# untitled.net
KiCad netlist of a schematic drawn in EAGLE
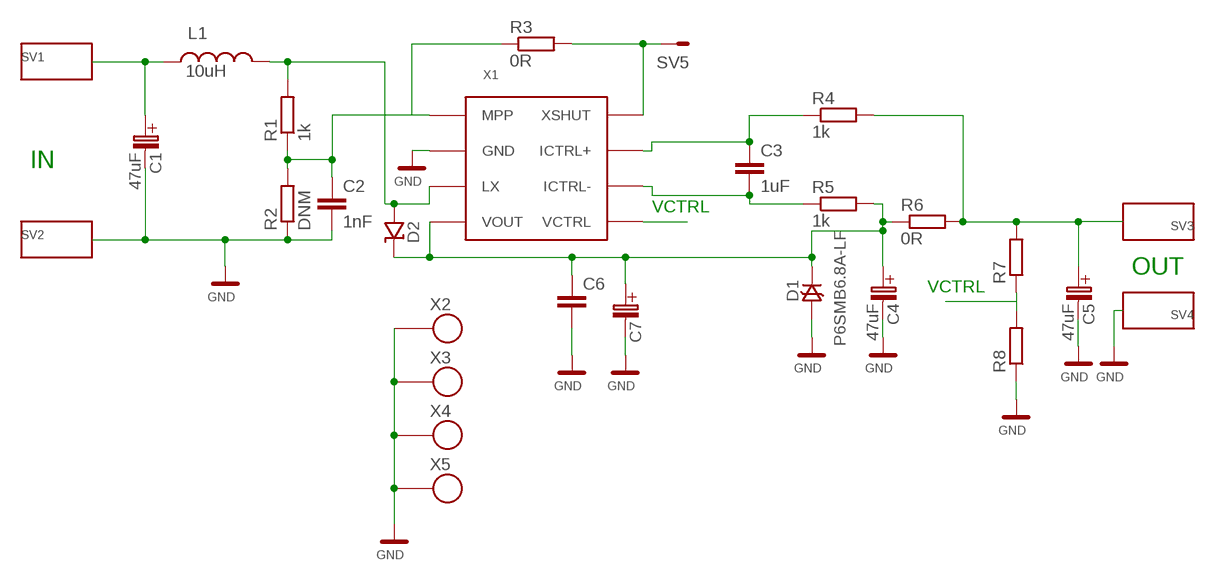
[diagram p0: schematic, sheet 1]

(export (version "E")
  (design (tool "Eeschema 10.0.6"))
  (components
    (comp (ref "C1") (value "47uF") (footprint "eagle-import:C") (libsource (lib "eagle-import") (part "C")))
    (comp (ref "C2")
      (value "1nF")
      (footprint "eagle-import:C0805")
      (libsource (lib "eagle-import") (part "C0805"))
    )
    (comp (ref "C3")
      (value "1uF")
      (footprint "eagle-import:C0805")
      (libsource (lib "eagle-import") (part "C0805"))
    )
    (comp (ref "C4") (value "47uF") (footprint "eagle-import:C") (libsource (lib "eagle-import") (part "C")))
    (comp (ref "C5") (value "47uF") (footprint "eagle-import:C") (libsource (lib "eagle-import") (part "C")))
    (comp (ref "C6")
      (value "C0805")
      (footprint "eagle-import:C0805")
      (libsource (lib "eagle-import") (part "C0805"))
    )
    (comp (ref "C7") (value "B") (footprint "eagle-import:B") (libsource (lib "eagle-import") (part "B")))
    (comp (ref "D1")
      (value "P6SMB6.8A-LF")
      (footprint "eagle-import:SMB")
      (libsource (lib "eagle-import") (part "D-TRANSIL"))
    )
    (comp (ref "D2")
      (value "D-SHOTKY-SMA")
      (footprint "eagle-import:SMA")
      (libsource (lib "eagle-import") (part "D-SHOTKY-SMA"))
    )
    (comp (ref "L1")
      (value "10uH")
      (footprint "eagle-import:DE1205-10")
      (libsource (lib "eagle-import") (part "DE1205-10"))
    )
    (comp (ref "R1")
      (value "1k")
      (footprint "eagle-import:0805")
      (libsource (lib "eagle-import") (part "R0805"))
    )
    (comp (ref "R2")
      (value "DNM")
      (footprint "eagle-import:0805")
      (libsource (lib "eagle-import") (part "R0805"))
    )
    (comp (ref "R3")
      (value "0R")
      (footprint "eagle-import:1206")
      (libsource (lib "eagle-import") (part "R1206"))
    )
    (comp (ref "R4")
      (value "1k")
      (footprint "eagle-import:0805")
      (libsource (lib "eagle-import") (part "R0805"))
    )
    (comp (ref "R5")
      (value "1k")
      (footprint "eagle-import:0805")
      (libsource (lib "eagle-import") (part "R0805"))
    )
    (comp (ref "R6")
      (value "0R")
      (footprint "eagle-import:1206")
      (libsource (lib "eagle-import") (part "R1206"))
    )
    (comp (ref "R7")
      (value "R0805")
      (footprint "eagle-import:0805")
      (libsource (lib "eagle-import") (part "R0805"))
    )
    (comp (ref "R8")
      (value "R0805")
      (footprint "eagle-import:0805")
      (libsource (lib "eagle-import") (part "R0805"))
    )
    (comp (ref "SV1")
      (value "WAGO256")
      (footprint "eagle-import:WAGO256")
      (libsource (lib "eagle-import") (part "WAGO256"))
    )
    (comp (ref "SV2")
      (value "WAGO256")
      (footprint "eagle-import:WAGO256")
      (libsource (lib "eagle-import") (part "WAGO256"))
    )
    (comp (ref "SV3")
      (value "WAGO256")
      (footprint "eagle-import:WAGO256")
      (libsource (lib "eagle-import") (part "WAGO256"))
    )
    (comp (ref "SV4")
      (value "WAGO256")
      (footprint "eagle-import:WAGO256")
      (libsource (lib "eagle-import") (part "WAGO256"))
    )
    (comp (ref "SV5")
      (value "MA01-1")
      (footprint "eagle-import:MA01-1")
      (libsource (lib "eagle-import") (part "MA01-1"))
    )
    (comp (ref "X1")
      (value "SPV1040")
      (footprint "eagle-import:TSSOP8")
      (libsource (lib "eagle-import") (part "SPV1040"))
    )
    (comp (ref "X2")
      (value "SROUB3M")
      (footprint "eagle-import:SROUB3M")
      (libsource (lib "eagle-import") (part "SROUB3M"))
    )
    (comp (ref "X3")
      (value "SROUB3M")
      (footprint "eagle-import:SROUB3M")
      (libsource (lib "eagle-import") (part "SROUB3M"))
    )
    (comp (ref "X4")
      (value "SROUB3M")
      (footprint "eagle-import:SROUB3M")
      (libsource (lib "eagle-import") (part "SROUB3M"))
    )
    (comp (ref "X5")
      (value "SROUB3M")
      (footprint "eagle-import:SROUB3M")
      (libsource (lib "eagle-import") (part "SROUB3M"))
    )
  )
  (nets
    (net (code "1") (name "/VCTRL") (class "Default")
      (node (ref "R7") (pin "1") (pinfunction "1_1") (pintype "passive"))
      (node (ref "R8") (pin "2") (pinfunction "2_2") (pintype "passive"))
      (node (ref "X1") (pin "5") (pinfunction "VCTRL_5") (pintype "bidirectional"))
    )
    (net (code "2") (name "GND") (class "Default")
      (node (ref "C1") (pin "-") (pinfunction "C_EL-_-") (pintype "passive"))
      (node (ref "C2") (pin "2") (pinfunction "2_2") (pintype "passive"))
      (node (ref "C4") (pin "-") (pinfunction "C_EL-_-") (pintype "passive"))
      (node (ref "C5") (pin "-") (pinfunction "C_EL-_-") (pintype "passive"))
      (node (ref "C6") (pin "2") (pinfunction "2_2") (pintype "passive"))
      (node (ref "C7") (pin "-") (pinfunction "C_EL-_-") (pintype "passive"))
      (node (ref "D1") (pin "A") (pinfunction "A_A") (pintype "passive"))
      (node (ref "R2") (pin "1") (pinfunction "1_1") (pintype "passive"))
      (node (ref "R8") (pin "1") (pinfunction "1_1") (pintype "passive"))
      (node (ref "SV2") (pin "1") (pinfunction "P$1_1") (pintype "passive"))
      (node (ref "SV2") (pin "A1") (pinfunction "P$1_A1") (pintype "passive"))
      (node (ref "SV4") (pin "1") (pinfunction "P$1_1") (pintype "passive"))
      (node (ref "SV4") (pin "A1") (pinfunction "P$1_A1") (pintype "passive"))
      (node (ref "X1") (pin "2") (pinfunction "GND_2") (pintype "bidirectional"))
      (node (ref "X2") (pin "P$1") (pinfunction "P$1_P$1") (pintype "bidirectional"))
      (node (ref "X3") (pin "P$1") (pinfunction "P$1_P$1") (pintype "bidirectional"))
      (node (ref "X4") (pin "P$1") (pinfunction "P$1_P$1") (pintype "bidirectional"))
      (node (ref "X5") (pin "P$1") (pinfunction "P$1_P$1") (pintype "bidirectional"))
    )
    (net (code "3") (name "Net-(C1-C_EL+)") (class "Default")
      (node (ref "C1") (pin "+") (pinfunction "C_EL+_+") (pintype "passive"))
      (node (ref "L1") (pin "P$1") (pinfunction "1_P$1") (pintype "passive"))
      (node (ref "SV1") (pin "1") (pinfunction "P$1_1") (pintype "passive"))
      (node (ref "SV1") (pin "A1") (pinfunction "P$1_A1") (pintype "passive"))
    )
    (net (code "4") (name "Net-(C4-C_EL+)") (class "Default")
      (node (ref "C4") (pin "+") (pinfunction "C_EL+_+") (pintype "passive"))
      (node (ref "C6") (pin "1") (pinfunction "1_1") (pintype "passive"))
      (node (ref "C7") (pin "+") (pinfunction "C_EL+_+") (pintype "passive"))
      (node (ref "D1") (pin "K") (pinfunction "K_K") (pintype "passive"))
      (node (ref "D2") (pin "K") (pinfunction "K_K") (pintype "passive"))
      (node (ref "R5") (pin "2") (pinfunction "2_2") (pintype "passive"))
      (node (ref "R6") (pin "1") (pinfunction "1_1") (pintype "passive"))
      (node (ref "X1") (pin "4") (pinfunction "VOUT_4") (pintype "bidirectional"))
    )
    (net (code "5") (name "Net-(C5-C_EL+)") (class "Default")
      (node (ref "C5") (pin "+") (pinfunction "C_EL+_+") (pintype "passive"))
      (node (ref "R4") (pin "2") (pinfunction "2_2") (pintype "passive"))
      (node (ref "R6") (pin "2") (pinfunction "2_2") (pintype "passive"))
      (node (ref "R7") (pin "2") (pinfunction "2_2") (pintype "passive"))
      (node (ref "SV3") (pin "1") (pinfunction "P$1_1") (pintype "passive"))
      (node (ref "SV3") (pin "A1") (pinfunction "P$1_A1") (pintype "passive"))
    )
    (net (code "6") (name "Net-(L1-2)") (class "Default")
      (node (ref "D2") (pin "A") (pinfunction "A_A") (pintype "passive"))
      (node (ref "L1") (pin "P$2") (pinfunction "2_P$2") (pintype "passive"))
      (node (ref "R1") (pin "2") (pinfunction "2_2") (pintype "passive"))
      (node (ref "X1") (pin "3") (pinfunction "LX_3") (pintype "bidirectional"))
    )
    (net (code "7") (name "Net-(SV5-P$1)") (class "Default")
      (node (ref "R3") (pin "2") (pinfunction "2_2") (pintype "passive"))
      (node (ref "SV5") (pin "1") (pinfunction "P$1_1") (pintype "passive"))
      (node (ref "X1") (pin "8") (pinfunction "XSHUT_8") (pintype "bidirectional"))
    )
    (net (code "8") (name "Net-(X1-ICTRL+)") (class "Default")
      (node (ref "C3") (pin "1") (pinfunction "1_1") (pintype "passive"))
      (node (ref "R4") (pin "1") (pinfunction "1_1") (pintype "passive"))
      (node (ref "X1") (pin "7") (pinfunction "ICTRL+_7") (pintype "bidirectional"))
    )
    (net (code "9") (name "Net-(X1-ICTRL-)") (class "Default")
      (node (ref "C3") (pin "2") (pinfunction "2_2") (pintype "passive"))
      (node (ref "R5") (pin "1") (pinfunction "1_1") (pintype "passive"))
      (node (ref "X1") (pin "6") (pinfunction "ICTRL-_6") (pintype "bidirectional"))
    )
    (net (code "10") (name "Net-(X1-MPP)") (class "Default")
      (node (ref "C2") (pin "1") (pinfunction "1_1") (pintype "passive"))
      (node (ref "R1") (pin "1") (pinfunction "1_1") (pintype "passive"))
      (node (ref "R2") (pin "2") (pinfunction "2_2") (pintype "passive"))
      (node (ref "R3") (pin "1") (pinfunction "1_1") (pintype "passive"))
      (node (ref "X1") (pin "1") (pinfunction "MPP_1") (pintype "bidirectional"))
    )
  )
)
